# 10_MeasOutUI.net
KiCad netlist of a schematic drawn in Altium Designer
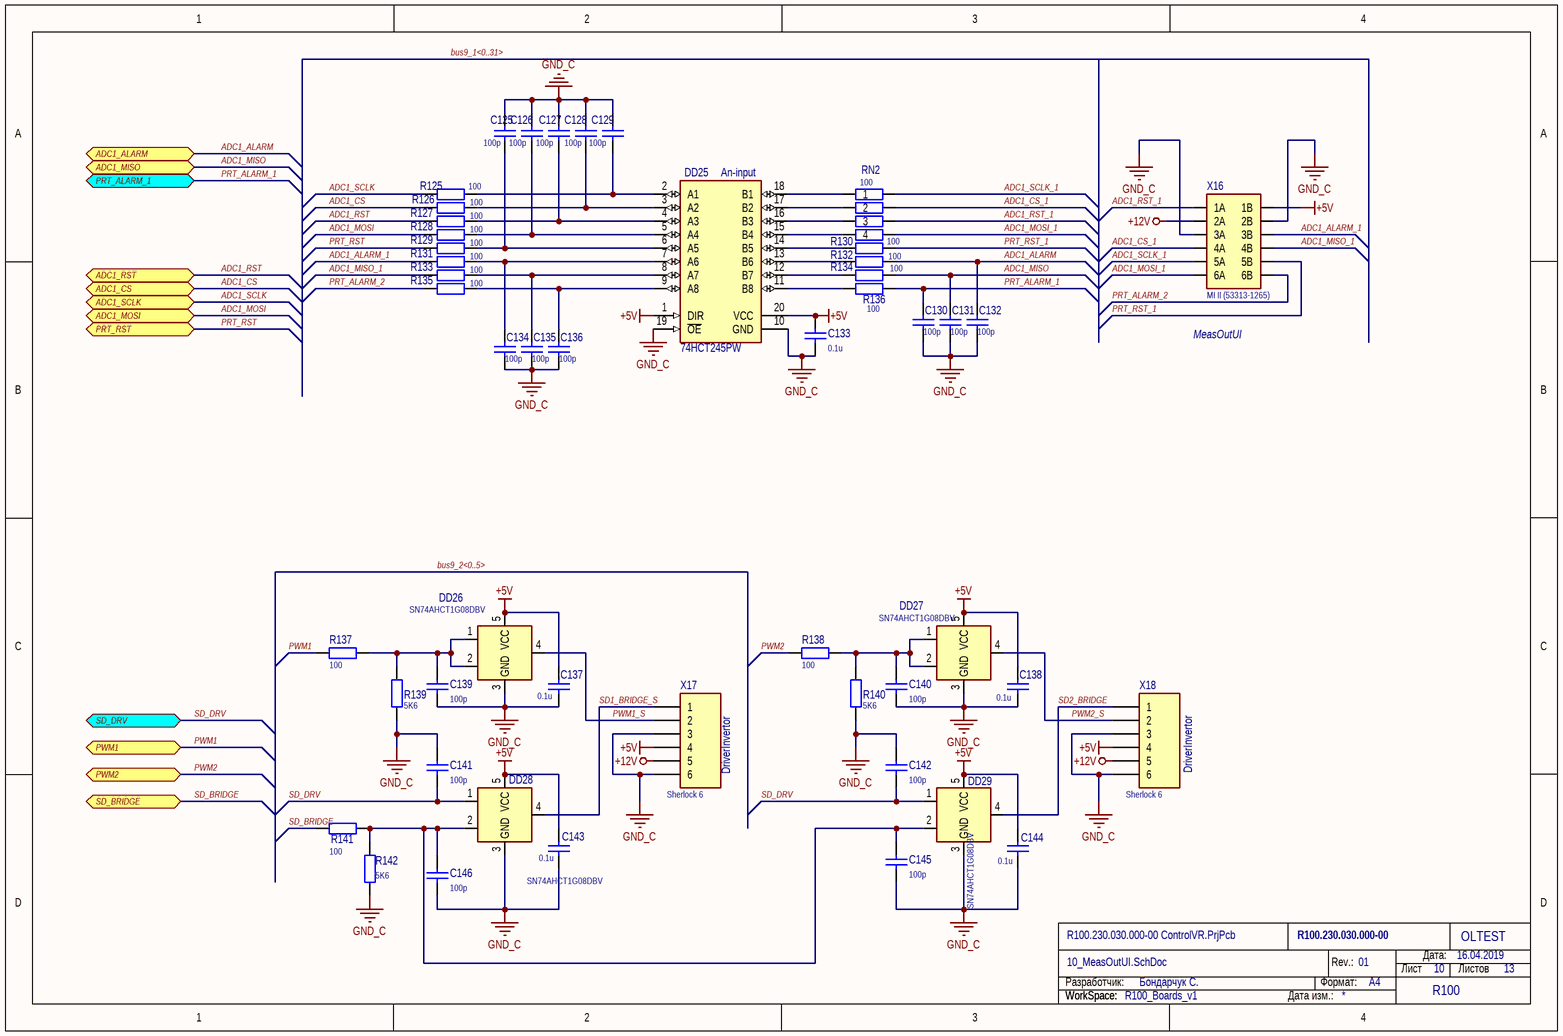
[diagram p0: 10_MeasOutUI.SchDoc]

(export (version "E")
  (design (tool "Eeschema 10.0.6"))
  (components
    (comp (ref "C125")
      (value "100p")
      (footprint "mainLib:SMD_C_0603")
      (description "SMD C 0603 MURATA 100V 5% NP0")
      (fields (field (name "PARTNUMBER") "GRM1885C2A101JA01") (field (name "MANUFACTURER") "MURATA"))
      (libsource (lib "mainRCLib") (part "C0603 100p 100V 5%"))
    )
    (comp (ref "C126")
      (value "100p")
      (footprint "mainLib:SMD_C_0603")
      (description "SMD C 0603 MURATA 100V 5% NP0")
      (fields (field (name "PARTNUMBER") "GRM1885C2A101JA01") (field (name "MANUFACTURER") "MURATA"))
      (libsource (lib "mainRCLib") (part "C0603 100p 100V 5%"))
    )
    (comp (ref "C127")
      (value "100p")
      (footprint "mainLib:SMD_C_0603")
      (description "SMD C 0603 MURATA 100V 5% NP0")
      (fields (field (name "PARTNUMBER") "GRM1885C2A101JA01") (field (name "MANUFACTURER") "MURATA"))
      (libsource (lib "mainRCLib") (part "C0603 100p 100V 5%"))
    )
    (comp (ref "C128")
      (value "100p")
      (footprint "mainLib:SMD_C_0603")
      (description "SMD C 0603 MURATA 100V 5% NP0")
      (fields (field (name "PARTNUMBER") "GRM1885C2A101JA01") (field (name "MANUFACTURER") "MURATA"))
      (libsource (lib "mainRCLib") (part "C0603 100p 100V 5%"))
    )
    (comp (ref "C129")
      (value "100p")
      (footprint "mainLib:SMD_C_0603")
      (description "SMD C 0603 MURATA 100V 5% NP0")
      (fields (field (name "PARTNUMBER") "GRM1885C2A101JA01") (field (name "MANUFACTURER") "MURATA"))
      (libsource (lib "mainRCLib") (part "C0603 100p 100V 5%"))
    )
    (comp (ref "C130")
      (value "100p")
      (footprint "mainLib:SMD_C_0603")
      (description "SMD C 0603 MURATA 100V 5% NP0")
      (fields (field (name "PARTNUMBER") "GRM1885C2A101JA01") (field (name "MANUFACTURER") "MURATA"))
      (libsource (lib "mainRCLib") (part "C0603 100p 100V 5%"))
    )
    (comp (ref "C131")
      (value "100p")
      (footprint "mainLib:SMD_C_0603")
      (description "SMD C 0603 MURATA 100V 5% NP0")
      (fields (field (name "PARTNUMBER") "GRM1885C2A101JA01") (field (name "MANUFACTURER") "MURATA"))
      (libsource (lib "mainRCLib") (part "C0603 100p 100V 5%"))
    )
    (comp (ref "C132")
      (value "100p")
      (footprint "mainLib:SMD_C_0603")
      (description "SMD C 0603 MURATA 100V 5% NP0")
      (fields (field (name "PARTNUMBER") "GRM1885C2A101JA01") (field (name "MANUFACTURER") "MURATA"))
      (libsource (lib "mainRCLib") (part "C0603 100p 100V 5%"))
    )
    (comp (ref "C133")
      (value "0.1u")
      (footprint "mainLib:SMD_C_0603")
      (description "SMD C 0603 MURATA 50V 10% X7R")
      (fields (field (name "PARTNUMBER") "GRM188R71H104K") (field (name "MANUFACTURER") "MURATA"))
      (libsource (lib "mainRCLib") (part "C0603 0.1u 50V 10%"))
    )
    (comp (ref "C134")
      (value "100p")
      (footprint "mainLib:SMD_C_0603")
      (description "SMD C 0603 MURATA 100V 5% NP0")
      (fields (field (name "PARTNUMBER") "GRM1885C2A101JA01") (field (name "MANUFACTURER") "MURATA"))
      (libsource (lib "mainRCLib") (part "C0603 100p 100V 5%"))
    )
    (comp (ref "C135")
      (value "100p")
      (footprint "mainLib:SMD_C_0603")
      (description "SMD C 0603 MURATA 100V 5% NP0")
      (fields (field (name "PARTNUMBER") "GRM1885C2A101JA01") (field (name "MANUFACTURER") "MURATA"))
      (libsource (lib "mainRCLib") (part "C0603 100p 100V 5%"))
    )
    (comp (ref "C136")
      (value "100p")
      (footprint "mainLib:SMD_C_0603")
      (description "SMD C 0603 MURATA 100V 5% NP0")
      (fields (field (name "PARTNUMBER") "GRM1885C2A101JA01") (field (name "MANUFACTURER") "MURATA"))
      (libsource (lib "mainRCLib") (part "C0603 100p 100V 5%"))
    )
    (comp (ref "C137")
      (value "0.1u")
      (footprint "mainLib:SMD_C_0603")
      (description "SMD C 0603 MURATA 50V 10% X7R")
      (fields (field (name "PARTNUMBER") "GRM188R71H104K") (field (name "MANUFACTURER") "MURATA"))
      (libsource (lib "mainRCLib") (part "C0603 0.1u 50V 10%"))
    )
    (comp (ref "C138")
      (value "0.1u")
      (footprint "mainLib:SMD_C_0603")
      (description "SMD C 0603 MURATA 50V 10% X7R")
      (fields (field (name "PARTNUMBER") "GRM188R71H104K") (field (name "MANUFACTURER") "MURATA"))
      (libsource (lib "mainRCLib") (part "C0603 0.1u 50V 10%"))
    )
    (comp (ref "C139")
      (value "100p")
      (footprint "mainLib:SMD_C_0603")
      (description "SMD C 0603 MURATA 100V 5% NP0")
      (fields (field (name "PARTNUMBER") "GRM1885C2A101JA01") (field (name "MANUFACTURER") "MURATA"))
      (libsource (lib "mainRCLib") (part "C0603 100p 100V 5%"))
    )
    (comp (ref "C140")
      (value "100p")
      (footprint "mainLib:SMD_C_0603")
      (description "SMD C 0603 MURATA 100V 5% NP0")
      (fields (field (name "PARTNUMBER") "GRM1885C2A101JA01") (field (name "MANUFACTURER") "MURATA"))
      (libsource (lib "mainRCLib") (part "C0603 100p 100V 5%"))
    )
    (comp (ref "C141")
      (value "100p")
      (footprint "mainLib:SMD_C_0603")
      (description "SMD C 0603 MURATA 100V 5% NP0")
      (fields (field (name "PARTNUMBER") "GRM1885C2A101JA01") (field (name "MANUFACTURER") "MURATA"))
      (libsource (lib "mainRCLib") (part "C0603 100p 100V 5%"))
    )
    (comp (ref "C142")
      (value "100p")
      (footprint "mainLib:SMD_C_0603")
      (description "SMD C 0603 MURATA 100V 5% NP0")
      (fields (field (name "PARTNUMBER") "GRM1885C2A101JA01") (field (name "MANUFACTURER") "MURATA"))
      (libsource (lib "mainRCLib") (part "C0603 100p 100V 5%"))
    )
    (comp (ref "C143")
      (value "0.1u")
      (footprint "mainLib:SMD_C_0603")
      (description "SMD C 0603 MURATA 50V 10% X7R")
      (fields (field (name "PARTNUMBER") "GRM188R71H104K") (field (name "MANUFACTURER") "MURATA"))
      (libsource (lib "mainRCLib") (part "C0603 0.1u 50V 10%"))
    )
    (comp (ref "C144")
      (value "0.1u")
      (footprint "mainLib:SMD_C_0603")
      (description "SMD C 0603 MURATA 50V 10% X7R")
      (fields (field (name "PARTNUMBER") "GRM188R71H104K") (field (name "MANUFACTURER") "MURATA"))
      (libsource (lib "mainRCLib") (part "C0603 0.1u 50V 10%"))
    )
    (comp (ref "C145")
      (value "100p")
      (footprint "mainLib:SMD_C_0603")
      (description "SMD C 0603 MURATA 100V 5% NP0")
      (fields (field (name "PARTNUMBER") "GRM1885C2A101JA01") (field (name "MANUFACTURER") "MURATA"))
      (libsource (lib "mainRCLib") (part "C0603 100p 100V 5%"))
    )
    (comp (ref "C146")
      (value "100p")
      (footprint "mainLib:SMD_C_0603")
      (description "SMD C 0603 MURATA 100V 5% NP0")
      (fields (field (name "PARTNUMBER") "GRM1885C2A101JA01") (field (name "MANUFACTURER") "MURATA"))
      (libsource (lib "mainRCLib") (part "C0603 100p 100V 5%"))
    )
    (comp (ref "DD25")
      (value "74HCT245PW")
      (footprint "mainLib:TSSOP20")
      (description "Octal Bus Transceivers With 3-State Outputs, PW0020A")
      (fields (field (name "MANUFACTURER") "NXP"))
      (libsource (lib "mainLib") (part "74HCT245PW"))
    )
    (comp (ref "DD26")
      (value "SN74AHCT1G08DBV")
      (footprint "mainLib:SOT-23(DBV)")
      (description "2-in AND")
      (fields (field (name "MANUFACTURER") "Texas Instruments"))
      (libsource (lib "mainLib") (part "SN74AHCT1G08DBV"))
    )
    (comp (ref "DD27")
      (value "SN74AHCT1G08DBV")
      (footprint "mainLib:SOT-23(DBV)")
      (description "2-in AND")
      (fields (field (name "MANUFACTURER") "Texas Instruments"))
      (libsource (lib "mainLib") (part "SN74AHCT1G08DBV"))
    )
    (comp (ref "DD28")
      (value "SN74AHCT1G08DBV")
      (footprint "mainLib:SOT-23(DBV)")
      (description "2-in AND")
      (fields (field (name "MANUFACTURER") "Texas Instruments"))
      (libsource (lib "mainLib") (part "SN74AHCT1G08DBV"))
    )
    (comp (ref "DD29")
      (value "SN74AHCT1G08DBV")
      (footprint "mainLib:SOT-23(DBV)")
      (description "2-in AND")
      (fields (field (name "MANUFACTURER") "Texas Instruments"))
      (libsource (lib "mainLib") (part "SN74AHCT1G08DBV"))
    )
    (comp (ref "R125")
      (value "100")
      (footprint "SMD_R_0603")
      (description "SMD R 0603 VISHAY 0.1W 75V 1% 100ppm")
      (fields (field (name "PARTNUMBER") "CRCW0603100RFK") (field (name "MANUFACTURER") "VISHAY"))
      (libsource (lib "mainRCLib") (part "R0603 100 1%"))
    )
    (comp (ref "R126")
      (value "100")
      (footprint "SMD_R_0603")
      (description "SMD R 0603 VISHAY 0.1W 75V 1% 100ppm")
      (fields (field (name "PARTNUMBER") "CRCW0603100RFK") (field (name "MANUFACTURER") "VISHAY"))
      (libsource (lib "mainRCLib") (part "R0603 100 1%"))
    )
    (comp (ref "R127")
      (value "100")
      (footprint "SMD_R_0603")
      (description "SMD R 0603 VISHAY 0.1W 75V 1% 100ppm")
      (fields (field (name "PARTNUMBER") "CRCW0603100RFK") (field (name "MANUFACTURER") "VISHAY"))
      (libsource (lib "mainRCLib") (part "R0603 100 1%"))
    )
    (comp (ref "R128")
      (value "100")
      (footprint "SMD_R_0603")
      (description "SMD R 0603 VISHAY 0.1W 75V 1% 100ppm")
      (fields (field (name "PARTNUMBER") "CRCW0603100RFK") (field (name "MANUFACTURER") "VISHAY"))
      (libsource (lib "mainRCLib") (part "R0603 100 1%"))
    )
    (comp (ref "R129")
      (value "100")
      (footprint "SMD_R_0603")
      (description "SMD R 0603 VISHAY 0.1W 75V 1% 100ppm")
      (fields (field (name "PARTNUMBER") "CRCW0603100RFK") (field (name "MANUFACTURER") "VISHAY"))
      (libsource (lib "mainRCLib") (part "R0603 100 1%"))
    )
    (comp (ref "R130")
      (value "100")
      (footprint "SMD_R_0603")
      (description "SMD R 0603 VISHAY 0.1W 75V 1% 100ppm")
      (fields (field (name "PARTNUMBER") "CRCW0603100RFK") (field (name "MANUFACTURER") "VISHAY"))
      (libsource (lib "mainRCLib") (part "R0603 100 1%"))
    )
    (comp (ref "R131")
      (value "100")
      (footprint "SMD_R_0603")
      (description "SMD R 0603 VISHAY 0.1W 75V 1% 100ppm")
      (fields (field (name "PARTNUMBER") "CRCW0603100RFK") (field (name "MANUFACTURER") "VISHAY"))
      (libsource (lib "mainRCLib") (part "R0603 100 1%"))
    )
    (comp (ref "R132")
      (value "100")
      (footprint "SMD_R_0603")
      (description "SMD R 0603 VISHAY 0.1W 75V 1% 100ppm")
      (fields (field (name "PARTNUMBER") "CRCW0603100RFK") (field (name "MANUFACTURER") "VISHAY"))
      (libsource (lib "mainRCLib") (part "R0603 100 1%"))
    )
    (comp (ref "R133")
      (value "100")
      (footprint "SMD_R_0603")
      (description "SMD R 0603 VISHAY 0.1W 75V 1% 100ppm")
      (fields (field (name "PARTNUMBER") "CRCW0603100RFK") (field (name "MANUFACTURER") "VISHAY"))
      (libsource (lib "mainRCLib") (part "R0603 100 1%"))
    )
    (comp (ref "R134")
      (value "100")
      (footprint "SMD_R_0603")
      (description "SMD R 0603 VISHAY 0.1W 75V 1% 100ppm")
      (fields (field (name "PARTNUMBER") "CRCW0603100RFK") (field (name "MANUFACTURER") "VISHAY"))
      (libsource (lib "mainRCLib") (part "R0603 100 1%"))
    )
    (comp (ref "R135")
      (value "100")
      (footprint "SMD_R_0603")
      (description "SMD R 0603 VISHAY 0.1W 75V 1% 100ppm")
      (fields (field (name "PARTNUMBER") "CRCW0603100RFK") (field (name "MANUFACTURER") "VISHAY"))
      (libsource (lib "mainRCLib") (part "R0603 100 1%"))
    )
    (comp (ref "R136")
      (value "100")
      (footprint "SMD_R_0603")
      (description "SMD R 0603 VISHAY 0.1W 75V 1% 100ppm")
      (fields (field (name "PARTNUMBER") "CRCW0603100RFK") (field (name "MANUFACTURER") "VISHAY"))
      (libsource (lib "mainRCLib") (part "R0603 100 1%"))
    )
    (comp (ref "R137")
      (value "100")
      (footprint "SMD_R_0603")
      (description "SMD R 0603 VISHAY 0.1W 75V 1% 100ppm")
      (fields (field (name "PARTNUMBER") "CRCW0603100RFK") (field (name "MANUFACTURER") "VISHAY"))
      (libsource (lib "mainRCLib") (part "R0603 100 1%"))
    )
    (comp (ref "R138")
      (value "100")
      (footprint "SMD_R_0603")
      (description "SMD R 0603 VISHAY 0.1W 75V 1% 100ppm")
      (fields (field (name "PARTNUMBER") "CRCW0603100RFK") (field (name "MANUFACTURER") "VISHAY"))
      (libsource (lib "mainRCLib") (part "R0603 100 1%"))
    )
    (comp (ref "R139")
      (value "5K6")
      (footprint "mainLib:SMD_R_0603")
      (description "SMD R 0603 VISHAY 0.1W 75V 1% 100ppm")
      (fields (field (name "PARTNUMBER") "CRCW06035K60FK") (field (name "MANUFACTURER") "VISHAY"))
      (libsource (lib "mainRCLib") (part "R0603 5K6 1%"))
    )
    (comp (ref "R140")
      (value "5K6")
      (footprint "mainLib:SMD_R_0603")
      (description "SMD R 0603 VISHAY 0.1W 75V 1% 100ppm")
      (fields (field (name "PARTNUMBER") "CRCW06035K60FK") (field (name "MANUFACTURER") "VISHAY"))
      (libsource (lib "mainRCLib") (part "R0603 5K6 1%"))
    )
    (comp (ref "R141")
      (value "100")
      (footprint "SMD_R_0603")
      (description "SMD R 0603 VISHAY 0.1W 75V 1% 100ppm")
      (fields (field (name "PARTNUMBER") "CRCW0603100RFK") (field (name "MANUFACTURER") "VISHAY"))
      (libsource (lib "mainRCLib") (part "R0603 100 1%"))
    )
    (comp (ref "R142")
      (value "5K6")
      (footprint "mainLib:SMD_R_0603")
      (description "SMD R 0603 VISHAY 0.1W 75V 1% 100ppm")
      (fields (field (name "PARTNUMBER") "CRCW06035K60FK") (field (name "MANUFACTURER") "VISHAY"))
      (libsource (lib "mainRCLib") (part "R0603 5K6 1%"))
    )
    (comp (ref "RN2")
      (value "100")
      (footprint "mainLib:CRA06S")
      (description "SMD RESISTOR ARRAY VISHAY 0.063W 50V 1% 100ppm")
      (fields (field (name "PARTNUMBER") "CRA06S083100RF") (field (name "MANUFACTURER") "VISHAY"))
      (libsource (lib "mainRCLib") (part "CRA06S 4x100 1%"))
    )
    (comp (ref "X16")
      (value "MI II (53313-1265)")
      (footprint "mainLib:53313-1265")
      (description "MI II 12 (6x2row), 2A 125V 2mm")
      (fields (field (name "PARTNUMBER") "53313-1265") (field (name "MANUFACTURER") "MOLEX"))
      (libsource (lib "mainLib") (part "53313-1265"))
    )
    (comp (ref "X17")
      (value "Sherlock 6")
      (footprint "mainLib:35362-0650")
      (description "Sherlock 6 Side, 2A 125V 2mm")
      (fields (field (name "PARTNUMBER") "35362-0650") (field (name "MANUFACTURER") "MOLEX"))
      (libsource (lib "mainLib") (part "35363-0650"))
    )
    (comp (ref "X18")
      (value "Sherlock 6")
      (footprint "mainLib:35362-0650")
      (description "Sherlock 6 Side, 2A 125V 2mm")
      (fields (field (name "PARTNUMBER") "35362-0650") (field (name "MANUFACTURER") "MOLEX"))
      (libsource (lib "mainLib") (part "35363-0650"))
    )
  )
  (nets
    (net (code "3") (name "+5V") (class "Default")
      (node (ref "C133") (pin "2") (pinfunction "2_2") (pintype "passive"))
      (node (ref "C137") (pin "2") (pinfunction "2_2") (pintype "passive"))
      (node (ref "C138") (pin "2") (pinfunction "2_2") (pintype "passive"))
      (node (ref "C143") (pin "2") (pinfunction "2_2") (pintype "passive"))
      (node (ref "C144") (pin "2") (pinfunction "2_2") (pintype "passive"))
      (node (ref "DD25") (pin "1") (pinfunction "DIR_1") (pintype "input"))
      (node (ref "DD25") (pin "20") (pinfunction "VCC_20") (pintype "power_in"))
      (node (ref "DD26") (pin "5") (pinfunction "VCC_5") (pintype "passive"))
      (node (ref "DD27") (pin "5") (pinfunction "VCC_5") (pintype "passive"))
      (node (ref "DD28") (pin "5") (pinfunction "VCC_5") (pintype "passive"))
      (node (ref "DD29") (pin "5") (pinfunction "VCC_5") (pintype "passive"))
      (node (ref "X16") (pin "1B") (pinfunction "1B_1B") (pintype "passive"))
      (node (ref "X17") (pin "4") (pinfunction "4_4") (pintype "passive"))
      (node (ref "X18") (pin "4") (pinfunction "4_4") (pintype "passive"))
    )
    (net (code "4") (name "+12V") (class "Default")
      (node (ref "X16") (pin "2A") (pinfunction "2A_2A") (pintype "passive"))
      (node (ref "X17") (pin "5") (pinfunction "5_5") (pintype "passive"))
      (node (ref "X18") (pin "5") (pinfunction "5_5") (pintype "passive"))
    )
    (net (code "5") (name "/ADC1_ALARM") (class "Default")
      (node (ref "C132") (pin "2") (pinfunction "2_2") (pintype "passive"))
      (node (ref "R132") (pin "2") (pinfunction "2_2") (pintype "passive"))
    )
    (net (code "6") (name "/ADC1_ALARM_1") (class "Default")
      (node (ref "R131") (pin "1") (pinfunction "1_1") (pintype "passive"))
      (node (ref "X16") (pin "3B") (pinfunction "3B_3B") (pintype "passive"))
    )
    (net (code "7") (name "/ADC1_CS") (class "Default")
      (node (ref "R126") (pin "1") (pinfunction "1_1") (pintype "passive"))
    )
    (net (code "8") (name "/ADC1_CS_1") (class "Default")
      (node (ref "RN2") (pin "7") (pinfunction "7_7") (pintype "passive"))
      (node (ref "X16") (pin "4A") (pinfunction "4A_4A") (pintype "passive"))
    )
    (net (code "9") (name "/ADC1_MISO") (class "Default")
      (node (ref "C131") (pin "2") (pinfunction "2_2") (pintype "passive"))
      (node (ref "R134") (pin "2") (pinfunction "2_2") (pintype "passive"))
    )
    (net (code "10") (name "/ADC1_MISO_1") (class "Default")
      (node (ref "R133") (pin "1") (pinfunction "1_1") (pintype "passive"))
      (node (ref "X16") (pin "4B") (pinfunction "4B_4B") (pintype "passive"))
    )
    (net (code "11") (name "/ADC1_MOSI") (class "Default")
      (node (ref "R128") (pin "1") (pinfunction "1_1") (pintype "passive"))
    )
    (net (code "12") (name "/ADC1_MOSI_1") (class "Default")
      (node (ref "RN2") (pin "5") (pinfunction "5_5") (pintype "passive"))
      (node (ref "X16") (pin "6A") (pinfunction "6A_6A") (pintype "passive"))
    )
    (net (code "13") (name "/ADC1_RST") (class "Default")
      (node (ref "R127") (pin "1") (pinfunction "1_1") (pintype "passive"))
    )
    (net (code "14") (name "/ADC1_RST_1") (class "Default")
      (node (ref "RN2") (pin "6") (pinfunction "6_6") (pintype "passive"))
      (node (ref "X16") (pin "1A") (pinfunction "1A_1A") (pintype "passive"))
    )
    (net (code "15") (name "/ADC1_SCLK") (class "Default")
      (node (ref "R125") (pin "1") (pinfunction "1_1") (pintype "passive"))
    )
    (net (code "16") (name "/ADC1_SCLK_1") (class "Default")
      (node (ref "RN2") (pin "8") (pinfunction "8_8") (pintype "passive"))
      (node (ref "X16") (pin "5A") (pinfunction "5A_5A") (pintype "passive"))
    )
    (net (code "17") (name "/PRT_ALARM_1") (class "Default")
      (node (ref "C130") (pin "2") (pinfunction "2_2") (pintype "passive"))
      (node (ref "R136") (pin "2") (pinfunction "2_2") (pintype "passive"))
    )
    (net (code "18") (name "/PRT_ALARM_2") (class "Default")
      (node (ref "R135") (pin "1") (pinfunction "1_1") (pintype "passive"))
      (node (ref "X16") (pin "6B") (pinfunction "6B_6B") (pintype "passive"))
    )
    (net (code "19") (name "/PRT_RST") (class "Default")
      (node (ref "R129") (pin "1") (pinfunction "1_1") (pintype "passive"))
    )
    (net (code "20") (name "/PRT_RST_1") (class "Default")
      (node (ref "R130") (pin "2") (pinfunction "2_2") (pintype "passive"))
      (node (ref "X16") (pin "5B") (pinfunction "5B_5B") (pintype "passive"))
    )
    (net (code "21") (name "/PWM1") (class "Default")
      (node (ref "R137") (pin "1") (pinfunction "1_1") (pintype "passive"))
    )
    (net (code "22") (name "/PWM1_S") (class "Default")
      (node (ref "DD26") (pin "4") (pintype "passive"))
      (node (ref "X17") (pin "2") (pinfunction "2_2") (pintype "passive"))
    )
    (net (code "23") (name "/PWM2") (class "Default")
      (node (ref "R138") (pin "1") (pinfunction "1_1") (pintype "passive"))
    )
    (net (code "24") (name "/PWM2_S") (class "Default")
      (node (ref "DD27") (pin "4") (pintype "passive"))
      (node (ref "X18") (pin "2") (pinfunction "2_2") (pintype "passive"))
    )
    (net (code "25") (name "/SD1_BRIDGE_S") (class "Default")
      (node (ref "DD28") (pin "4") (pintype "passive"))
      (node (ref "X17") (pin "1") (pinfunction "1_1") (pintype "passive"))
    )
    (net (code "26") (name "/SD2_BRIDGE") (class "Default")
      (node (ref "DD29") (pin "4") (pintype "passive"))
      (node (ref "X18") (pin "1") (pinfunction "1_1") (pintype "passive"))
    )
    (net (code "27") (name "/SD_BRIDGE") (class "Default")
      (node (ref "R141") (pin "1") (pinfunction "1_1") (pintype "passive"))
    )
    (net (code "28") (name "/SD_DRV") (class "Default")
      (node (ref "C141") (pin "1") (pinfunction "1_1") (pintype "passive"))
      (node (ref "C142") (pin "1") (pinfunction "1_1") (pintype "passive"))
      (node (ref "DD28") (pin "1") (pintype "passive"))
      (node (ref "DD29") (pin "1") (pintype "passive"))
    )
    (net (code "31") (name "GND_C") (class "Default")
      (node (ref "C125") (pin "1") (pinfunction "1_1") (pintype "passive"))
      (node (ref "C126") (pin "1") (pinfunction "1_1") (pintype "passive"))
      (node (ref "C127") (pin "1") (pinfunction "1_1") (pintype "passive"))
      (node (ref "C128") (pin "1") (pinfunction "1_1") (pintype "passive"))
      (node (ref "C129") (pin "1") (pinfunction "1_1") (pintype "passive"))
      (node (ref "C130") (pin "1") (pinfunction "1_1") (pintype "passive"))
      (node (ref "C131") (pin "1") (pinfunction "1_1") (pintype "passive"))
      (node (ref "C132") (pin "1") (pinfunction "1_1") (pintype "passive"))
      (node (ref "C133") (pin "1") (pinfunction "1_1") (pintype "passive"))
      (node (ref "C134") (pin "1") (pinfunction "1_1") (pintype "passive"))
      (node (ref "C135") (pin "1") (pinfunction "1_1") (pintype "passive"))
      (node (ref "C136") (pin "1") (pinfunction "1_1") (pintype "passive"))
      (node (ref "C137") (pin "1") (pinfunction "1_1") (pintype "passive"))
      (node (ref "C138") (pin "1") (pinfunction "1_1") (pintype "passive"))
      (node (ref "C139") (pin "1") (pinfunction "1_1") (pintype "passive"))
      (node (ref "C140") (pin "1") (pinfunction "1_1") (pintype "passive"))
      (node (ref "C141") (pin "2") (pinfunction "2_2") (pintype "passive"))
      (node (ref "C142") (pin "2") (pinfunction "2_2") (pintype "passive"))
      (node (ref "C143") (pin "1") (pinfunction "1_1") (pintype "passive"))
      (node (ref "C144") (pin "1") (pinfunction "1_1") (pintype "passive"))
      (node (ref "C145") (pin "1") (pinfunction "1_1") (pintype "passive"))
      (node (ref "C146") (pin "1") (pinfunction "1_1") (pintype "passive"))
      (node (ref "DD25") (pin "10") (pinfunction "GND_10") (pintype "power_in"))
      (node (ref "DD25") (pin "19") (pinfunction "~{OE}_19") (pintype "input"))
      (node (ref "DD26") (pin "3") (pinfunction "GND_3") (pintype "passive"))
      (node (ref "DD27") (pin "3") (pinfunction "GND_3") (pintype "passive"))
      (node (ref "DD28") (pin "3") (pinfunction "GND_3") (pintype "passive"))
      (node (ref "DD29") (pin "3") (pinfunction "GND_3") (pintype "passive"))
      (node (ref "R139") (pin "1") (pinfunction "1_1") (pintype "passive"))
      (node (ref "R140") (pin "1") (pinfunction "1_1") (pintype "passive"))
      (node (ref "R142") (pin "1") (pinfunction "1_1") (pintype "passive"))
      (node (ref "X16") (pin "2B") (pinfunction "2B_2B") (pintype "passive"))
      (node (ref "X16") (pin "3A") (pinfunction "3A_3A") (pintype "passive"))
      (node (ref "X17") (pin "3") (pinfunction "3_3") (pintype "passive"))
      (node (ref "X17") (pin "6") (pinfunction "6_6") (pintype "passive"))
      (node (ref "X18") (pin "3") (pinfunction "3_3") (pintype "passive"))
      (node (ref "X18") (pin "6") (pinfunction "6_6") (pintype "passive"))
    )
    (net (code "32") (name "Net-(C139-Pad2)") (class "Default")
      (node (ref "C139") (pin "2") (pinfunction "2_2") (pintype "passive"))
      (node (ref "DD26") (pin "1") (pintype "passive"))
      (node (ref "DD26") (pin "2") (pintype "passive"))
      (node (ref "R137") (pin "2") (pinfunction "2_2") (pintype "passive"))
      (node (ref "R139") (pin "2") (pinfunction "2_2") (pintype "passive"))
    )
    (net (code "33") (name "Net-(C140-Pad2)") (class "Default")
      (node (ref "C140") (pin "2") (pinfunction "2_2") (pintype "passive"))
      (node (ref "DD27") (pin "1") (pintype "passive"))
      (node (ref "DD27") (pin "2") (pintype "passive"))
      (node (ref "R138") (pin "2") (pinfunction "2_2") (pintype "passive"))
      (node (ref "R140") (pin "2") (pinfunction "2_2") (pintype "passive"))
    )
    (net (code "34") (name "Net-(C145-Pad2)") (class "Default")
      (node (ref "C145") (pin "2") (pinfunction "2_2") (pintype "passive"))
      (node (ref "C146") (pin "2") (pinfunction "2_2") (pintype "passive"))
      (node (ref "DD28") (pin "2") (pintype "passive"))
      (node (ref "DD29") (pin "2") (pintype "passive"))
      (node (ref "R141") (pin "2") (pinfunction "2_2") (pintype "passive"))
      (node (ref "R142") (pin "2") (pinfunction "2_2") (pintype "passive"))
    )
    (net (code "35") (name "Net-(DD25-A1)") (class "Default")
      (node (ref "C129") (pin "2") (pinfunction "2_2") (pintype "passive"))
      (node (ref "DD25") (pin "2") (pinfunction "A1_2") (pintype "bidirectional"))
      (node (ref "R125") (pin "2") (pinfunction "2_2") (pintype "passive"))
    )
    (net (code "36") (name "Net-(DD25-A2)") (class "Default")
      (node (ref "C128") (pin "2") (pinfunction "2_2") (pintype "passive"))
      (node (ref "DD25") (pin "3") (pinfunction "A2_3") (pintype "bidirectional"))
      (node (ref "R126") (pin "2") (pinfunction "2_2") (pintype "passive"))
    )
    (net (code "37") (name "Net-(DD25-A3)") (class "Default")
      (node (ref "C127") (pin "2") (pinfunction "2_2") (pintype "passive"))
      (node (ref "DD25") (pin "4") (pinfunction "A3_4") (pintype "bidirectional"))
      (node (ref "R127") (pin "2") (pinfunction "2_2") (pintype "passive"))
    )
    (net (code "38") (name "Net-(DD25-A4)") (class "Default")
      (node (ref "C126") (pin "2") (pinfunction "2_2") (pintype "passive"))
      (node (ref "DD25") (pin "5") (pinfunction "A4_5") (pintype "bidirectional"))
      (node (ref "R128") (pin "2") (pinfunction "2_2") (pintype "passive"))
    )
    (net (code "39") (name "Net-(DD25-A5)") (class "Default")
      (node (ref "C125") (pin "2") (pinfunction "2_2") (pintype "passive"))
      (node (ref "DD25") (pin "6") (pinfunction "A5_6") (pintype "bidirectional"))
      (node (ref "R129") (pin "2") (pinfunction "2_2") (pintype "passive"))
    )
    (net (code "40") (name "Net-(DD25-A6)") (class "Default")
      (node (ref "C134") (pin "2") (pinfunction "2_2") (pintype "passive"))
      (node (ref "DD25") (pin "7") (pinfunction "A6_7") (pintype "bidirectional"))
      (node (ref "R131") (pin "2") (pinfunction "2_2") (pintype "passive"))
    )
    (net (code "41") (name "Net-(DD25-A7)") (class "Default")
      (node (ref "C135") (pin "2") (pinfunction "2_2") (pintype "passive"))
      (node (ref "DD25") (pin "8") (pinfunction "A7_8") (pintype "bidirectional"))
      (node (ref "R133") (pin "2") (pinfunction "2_2") (pintype "passive"))
    )
    (net (code "42") (name "Net-(DD25-A8)") (class "Default")
      (node (ref "C136") (pin "2") (pinfunction "2_2") (pintype "passive"))
      (node (ref "DD25") (pin "9") (pinfunction "A8_9") (pintype "bidirectional"))
      (node (ref "R135") (pin "2") (pinfunction "2_2") (pintype "passive"))
    )
    (net (code "43") (name "Net-(DD25-B1)") (class "Default")
      (node (ref "DD25") (pin "18") (pinfunction "B1_18") (pintype "bidirectional"))
      (node (ref "RN2") (pin "1") (pinfunction "1_1") (pintype "passive"))
    )
    (net (code "44") (name "Net-(DD25-B2)") (class "Default")
      (node (ref "DD25") (pin "17") (pinfunction "B2_17") (pintype "bidirectional"))
      (node (ref "RN2") (pin "2") (pinfunction "2_2") (pintype "passive"))
    )
    (net (code "45") (name "Net-(DD25-B3)") (class "Default")
      (node (ref "DD25") (pin "16") (pinfunction "B3_16") (pintype "bidirectional"))
      (node (ref "RN2") (pin "3") (pinfunction "3_3") (pintype "passive"))
    )
    (net (code "46") (name "Net-(DD25-B4)") (class "Default")
      (node (ref "DD25") (pin "15") (pinfunction "B4_15") (pintype "bidirectional"))
      (node (ref "RN2") (pin "4") (pinfunction "4_4") (pintype "passive"))
    )
    (net (code "47") (name "Net-(DD25-B5)") (class "Default")
      (node (ref "DD25") (pin "14") (pinfunction "B5_14") (pintype "bidirectional"))
      (node (ref "R130") (pin "1") (pinfunction "1_1") (pintype "passive"))
    )
    (net (code "48") (name "Net-(DD25-B6)") (class "Default")
      (node (ref "DD25") (pin "13") (pinfunction "B6_13") (pintype "bidirectional"))
      (node (ref "R132") (pin "1") (pinfunction "1_1") (pintype "passive"))
    )
    (net (code "49") (name "Net-(DD25-B7)") (class "Default")
      (node (ref "DD25") (pin "12") (pinfunction "B7_12") (pintype "bidirectional"))
      (node (ref "R134") (pin "1") (pinfunction "1_1") (pintype "passive"))
    )
    (net (code "50") (name "Net-(DD25-B8)") (class "Default")
      (node (ref "DD25") (pin "11") (pinfunction "B8_11") (pintype "bidirectional"))
      (node (ref "R136") (pin "1") (pinfunction "1_1") (pintype "passive"))
    )
  )
)
